# jetson.net
KiCad netlist of a schematic drawn in EAGLE
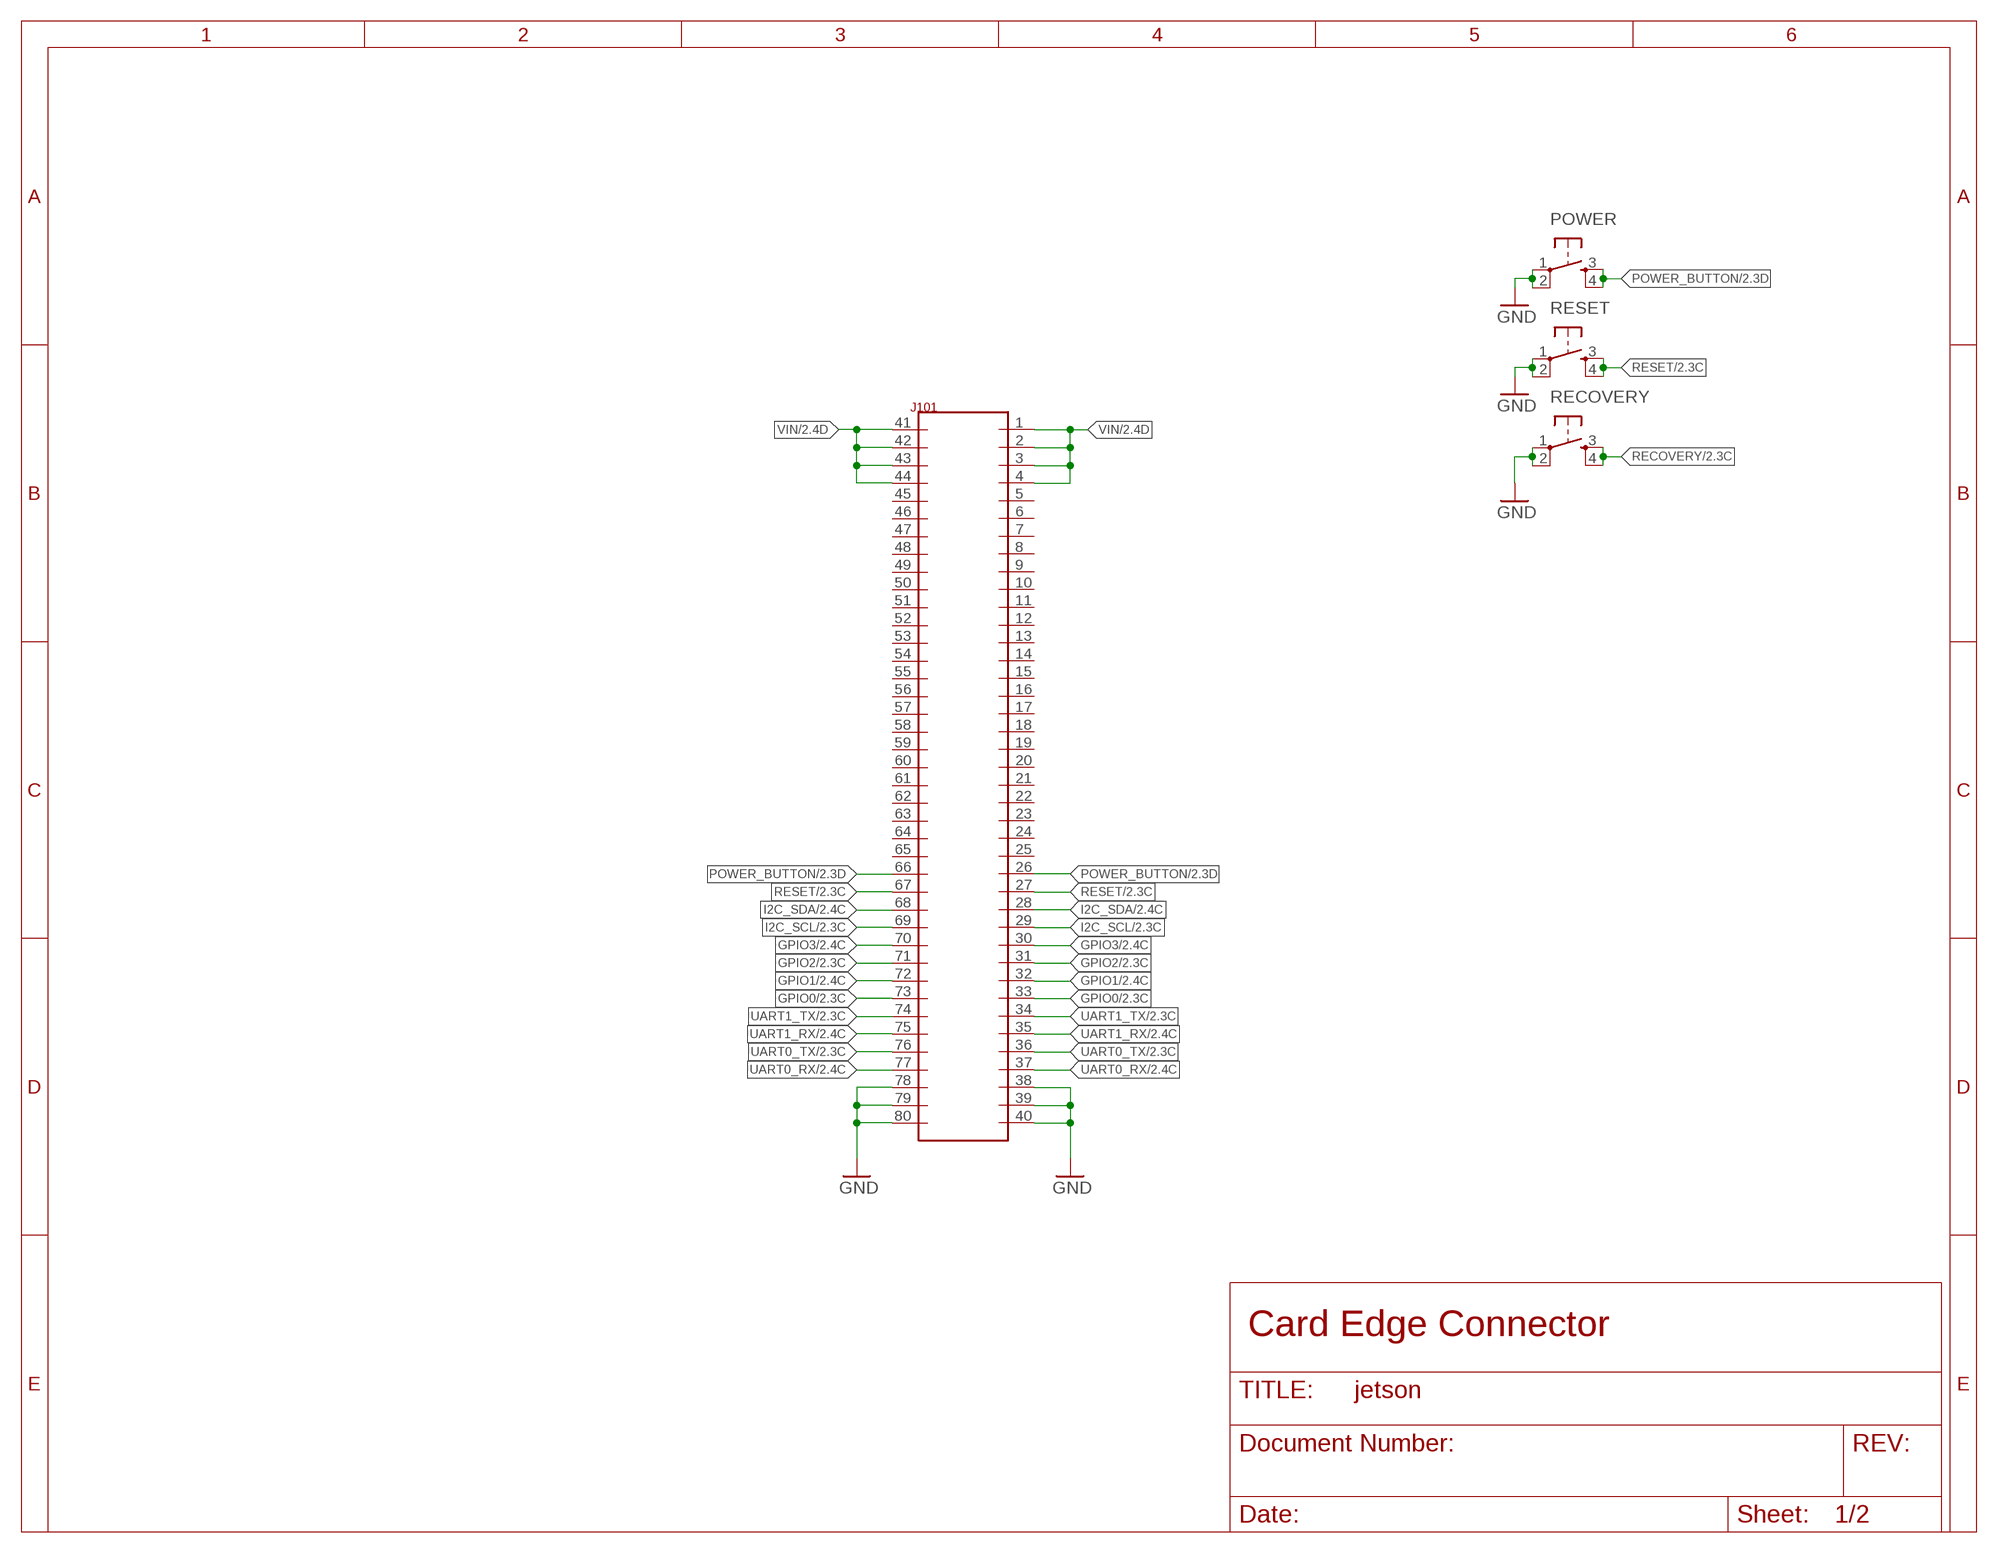
[diagram p0: schematic, sheet 1]
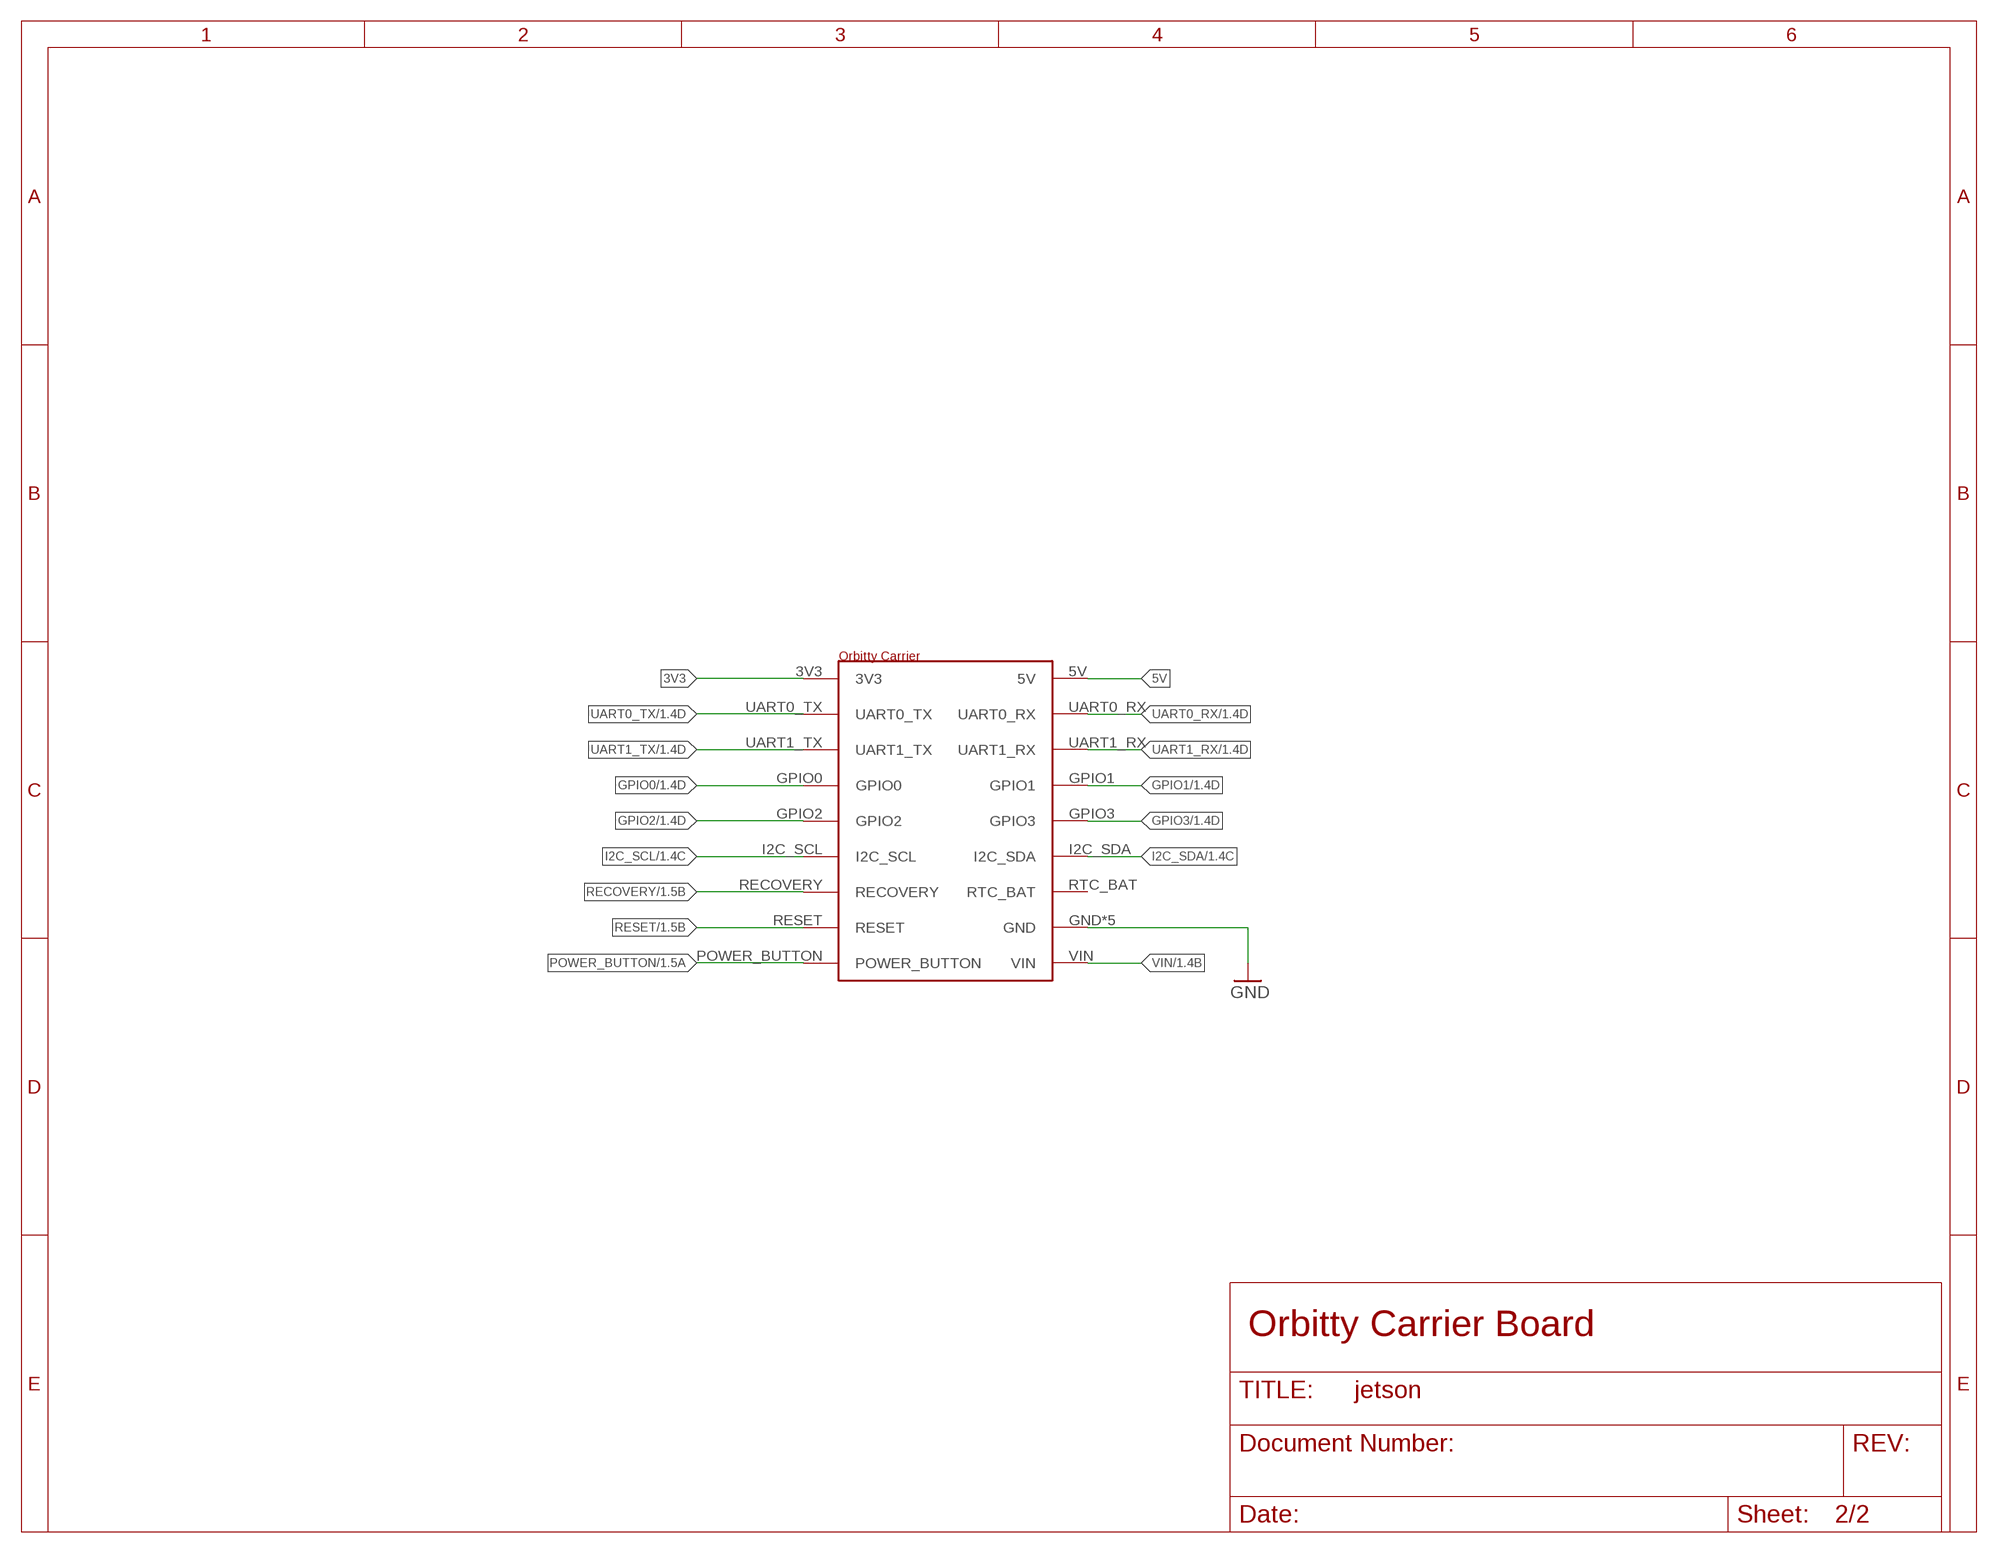
[diagram p1: schematic, sheet 2]

(export (version "E")
  (design (tool "Eeschema 10.0.6"))
  (components
    (comp (ref "U$1")
      (value "ORBITTY_CARRIER")
      (footprint "eagle-import:ORBITTY_CARRIER")
      (libsource (lib "eagle-import") (part "ORBITTY_CARRIER"))
    )
    (comp (ref "J101")
      (value "80-PIN-CARD-EDGE")
      (footprint "eagle-import:80-PIN-CARD-EDGE")
      (libsource (lib "eagle-import") (part "80-PIN-CARD-EDGE"))
    )
    (comp (ref "POWER")
      (value "TAC_SWITCHPTH")
      (footprint "eagle-import:TACTILE-PTH")
      (libsource (lib "eagle-import") (part "TAC_SWITCHPTH"))
    )
    (comp (ref "RECOVERY")
      (value "TAC_SWITCHPTH")
      (footprint "eagle-import:TACTILE-PTH")
      (libsource (lib "eagle-import") (part "TAC_SWITCHPTH"))
    )
    (comp (ref "RESET")
      (value "TAC_SWITCHPTH")
      (footprint "eagle-import:TACTILE-PTH")
      (libsource (lib "eagle-import") (part "TAC_SWITCHPTH"))
    )
  )
  (nets
    (net (code "1") (name "3V3") (class "Default")
      (node (ref "U$1") (pin "3V3") (pinfunction "3V3_3V3") (pintype "bidirectional"))
    )
    (net (code "2") (name "5V") (class "Default")
      (node (ref "U$1") (pin "5V") (pinfunction "5V_5V") (pintype "bidirectional"))
    )
    (net (code "3") (name "GND") (class "Default")
      (node (ref "J101") (pin "38") (pinfunction "P$38_38") (pintype "bidirectional"))
      (node (ref "J101") (pin "39") (pinfunction "P$39_39") (pintype "bidirectional"))
      (node (ref "J101") (pin "40") (pinfunction "P$40_40") (pintype "bidirectional"))
      (node (ref "J101") (pin "78") (pinfunction "P$78_78") (pintype "bidirectional"))
      (node (ref "J101") (pin "79") (pinfunction "P$79_79") (pintype "bidirectional"))
      (node (ref "J101") (pin "80") (pinfunction "P$80_80") (pintype "bidirectional"))
      (node (ref "POWER") (pin "1") (pinfunction "1_1") (pintype "passive"))
      (node (ref "POWER") (pin "2") (pinfunction "2_2") (pintype "passive"))
      (node (ref "RECOVERY") (pin "1") (pinfunction "1_1") (pintype "passive"))
      (node (ref "RECOVERY") (pin "2") (pinfunction "2_2") (pintype "passive"))
      (node (ref "RESET") (pin "1") (pinfunction "1_1") (pintype "passive"))
      (node (ref "RESET") (pin "2") (pinfunction "2_2") (pintype "passive"))
      (node (ref "U$1") (pin "GND") (pinfunction "GND_GND") (pintype "bidirectional"))
      (node (ref "U$1") (pin "GND1") (pinfunction "GND_GND1") (pintype "bidirectional"))
      (node (ref "U$1") (pin "GND2") (pinfunction "GND_GND2") (pintype "bidirectional"))
      (node (ref "U$1") (pin "GND3") (pinfunction "GND_GND3") (pintype "bidirectional"))
      (node (ref "U$1") (pin "GND4") (pinfunction "GND_GND4") (pintype "bidirectional"))
    )
    (net (code "4") (name "GPIO0") (class "Default")
      (node (ref "J101") (pin "33") (pinfunction "P$33_33") (pintype "bidirectional"))
      (node (ref "J101") (pin "73") (pinfunction "P$73_73") (pintype "bidirectional"))
      (node (ref "U$1") (pin "GPIO0") (pinfunction "GPIO0_GPIO0") (pintype "bidirectional"))
    )
    (net (code "5") (name "GPIO1") (class "Default")
      (node (ref "J101") (pin "32") (pinfunction "P$32_32") (pintype "bidirectional"))
      (node (ref "J101") (pin "72") (pinfunction "P$72_72") (pintype "bidirectional"))
      (node (ref "U$1") (pin "GPIO1") (pinfunction "GPIO1_GPIO1") (pintype "bidirectional"))
    )
    (net (code "6") (name "GPIO2") (class "Default")
      (node (ref "J101") (pin "31") (pinfunction "P$31_31") (pintype "bidirectional"))
      (node (ref "J101") (pin "71") (pinfunction "P$71_71") (pintype "bidirectional"))
      (node (ref "U$1") (pin "GPIO2") (pinfunction "GPIO2_GPIO2") (pintype "bidirectional"))
    )
    (net (code "7") (name "GPIO3") (class "Default")
      (node (ref "J101") (pin "30") (pinfunction "P$30_30") (pintype "bidirectional"))
      (node (ref "J101") (pin "70") (pinfunction "P$70_70") (pintype "bidirectional"))
      (node (ref "U$1") (pin "GPIO3") (pinfunction "GPIO3_GPIO3") (pintype "bidirectional"))
    )
    (net (code "8") (name "I2C_SCL") (class "Default")
      (node (ref "J101") (pin "29") (pinfunction "P$29_29") (pintype "bidirectional"))
      (node (ref "J101") (pin "69") (pinfunction "P$69_69") (pintype "bidirectional"))
      (node (ref "U$1") (pin "I2C_SCL") (pinfunction "I2C_SCL_I2C_SCL") (pintype "bidirectional"))
    )
    (net (code "9") (name "I2C_SDA") (class "Default")
      (node (ref "J101") (pin "28") (pinfunction "P$28_28") (pintype "bidirectional"))
      (node (ref "J101") (pin "68") (pinfunction "P$68_68") (pintype "bidirectional"))
      (node (ref "U$1") (pin "I2C_SDA") (pinfunction "I2C_SDA_I2C_SDA") (pintype "bidirectional"))
    )
    (net (code "10") (name "POWER_BUTTON") (class "Default")
      (node (ref "J101") (pin "26") (pinfunction "P$26_26") (pintype "bidirectional"))
      (node (ref "J101") (pin "66") (pinfunction "P$66_66") (pintype "bidirectional"))
      (node (ref "POWER") (pin "3") (pinfunction "3_3") (pintype "passive"))
      (node (ref "POWER") (pin "4") (pinfunction "4_4") (pintype "passive"))
      (node (ref "U$1") (pin "POWER_BUTTON") (pinfunction "POWER_BUTTON_POWER_BUTTON") (pintype "bidirectional"))
    )
    (net (code "11") (name "RECOVERY") (class "Default")
      (node (ref "RECOVERY") (pin "3") (pinfunction "3_3") (pintype "passive"))
      (node (ref "RECOVERY") (pin "4") (pinfunction "4_4") (pintype "passive"))
      (node (ref "U$1") (pin "RECOVERY") (pinfunction "RECOVERY_RECOVERY") (pintype "bidirectional"))
    )
    (net (code "12") (name "RESET") (class "Default")
      (node (ref "J101") (pin "27") (pinfunction "P$27_27") (pintype "bidirectional"))
      (node (ref "J101") (pin "67") (pinfunction "P$67_67") (pintype "bidirectional"))
      (node (ref "RESET") (pin "3") (pinfunction "3_3") (pintype "passive"))
      (node (ref "RESET") (pin "4") (pinfunction "4_4") (pintype "passive"))
      (node (ref "U$1") (pin "RESET") (pinfunction "RESET_RESET") (pintype "bidirectional"))
    )
    (net (code "13") (name "UART0_RX") (class "Default")
      (node (ref "J101") (pin "37") (pinfunction "P$37_37") (pintype "bidirectional"))
      (node (ref "J101") (pin "77") (pinfunction "P$77_77") (pintype "bidirectional"))
      (node (ref "U$1") (pin "UART0_RX") (pinfunction "UART0_RX_UART0_RX") (pintype "bidirectional"))
    )
    (net (code "14") (name "UART0_TX") (class "Default")
      (node (ref "J101") (pin "36") (pinfunction "P$36_36") (pintype "bidirectional"))
      (node (ref "J101") (pin "76") (pinfunction "P$76_76") (pintype "bidirectional"))
      (node (ref "U$1") (pin "UART0_TX") (pinfunction "UART0_TX_UART0_TX") (pintype "bidirectional"))
    )
    (net (code "15") (name "UART1_RX") (class "Default")
      (node (ref "J101") (pin "35") (pinfunction "P$35_35") (pintype "bidirectional"))
      (node (ref "J101") (pin "75") (pinfunction "P$75_75") (pintype "bidirectional"))
      (node (ref "U$1") (pin "UART1_RX") (pinfunction "UART1_RX_UART1_RX") (pintype "bidirectional"))
    )
    (net (code "16") (name "UART1_TX") (class "Default")
      (node (ref "J101") (pin "34") (pinfunction "P$34_34") (pintype "bidirectional"))
      (node (ref "J101") (pin "74") (pinfunction "P$74_74") (pintype "bidirectional"))
      (node (ref "U$1") (pin "UART1_TX") (pinfunction "UART1_TX_UART1_TX") (pintype "bidirectional"))
    )
    (net (code "17") (name "VIN") (class "Default")
      (node (ref "J101") (pin "1") (pinfunction "P$1_1") (pintype "bidirectional"))
      (node (ref "J101") (pin "2") (pinfunction "P$2_2") (pintype "bidirectional"))
      (node (ref "J101") (pin "3") (pinfunction "P$3_3") (pintype "bidirectional"))
      (node (ref "J101") (pin "4") (pinfunction "P$4_4") (pintype "bidirectional"))
      (node (ref "J101") (pin "41") (pinfunction "P$41_41") (pintype "bidirectional"))
      (node (ref "J101") (pin "42") (pinfunction "P$42_42") (pintype "bidirectional"))
      (node (ref "J101") (pin "43") (pinfunction "P$43_43") (pintype "bidirectional"))
      (node (ref "J101") (pin "44") (pinfunction "P$44_44") (pintype "bidirectional"))
      (node (ref "U$1") (pin "VIN") (pinfunction "VIN_VIN") (pintype "bidirectional"))
    )
    (net (code "18") (name "unconnected-(J101-P$5-Pad5)") (class "Default")
      (node (ref "J101") (pin "5") (pinfunction "P$5_5") (pintype "bidirectional"))
    )
    (net (code "19") (name "unconnected-(J101-P$6-Pad6)") (class "Default")
      (node (ref "J101") (pin "6") (pinfunction "P$6_6") (pintype "bidirectional"))
    )
    (net (code "20") (name "unconnected-(J101-P$7-Pad7)") (class "Default")
      (node (ref "J101") (pin "7") (pinfunction "P$7_7") (pintype "bidirectional"))
    )
    (net (code "21") (name "unconnected-(J101-P$8-Pad8)") (class "Default")
      (node (ref "J101") (pin "8") (pinfunction "P$8_8") (pintype "bidirectional"))
    )
    (net (code "22") (name "unconnected-(J101-P$9-Pad9)") (class "Default")
      (node (ref "J101") (pin "9") (pinfunction "P$9_9") (pintype "bidirectional"))
    )
    (net (code "23") (name "unconnected-(J101-P$10-Pad10)") (class "Default")
      (node (ref "J101") (pin "10") (pinfunction "P$10_10") (pintype "bidirectional"))
    )
    (net (code "24") (name "unconnected-(J101-P$11-Pad11)") (class "Default")
      (node (ref "J101") (pin "11") (pinfunction "P$11_11") (pintype "bidirectional"))
    )
    (net (code "25") (name "unconnected-(J101-P$12-Pad12)") (class "Default")
      (node (ref "J101") (pin "12") (pinfunction "P$12_12") (pintype "bidirectional"))
    )
    (net (code "26") (name "unconnected-(J101-P$13-Pad13)") (class "Default")
      (node (ref "J101") (pin "13") (pinfunction "P$13_13") (pintype "bidirectional"))
    )
    (net (code "27") (name "unconnected-(J101-P$14-Pad14)") (class "Default")
      (node (ref "J101") (pin "14") (pinfunction "P$14_14") (pintype "bidirectional"))
    )
    (net (code "28") (name "unconnected-(J101-P$15-Pad15)") (class "Default")
      (node (ref "J101") (pin "15") (pinfunction "P$15_15") (pintype "bidirectional"))
    )
    (net (code "29") (name "unconnected-(J101-P$16-Pad16)") (class "Default")
      (node (ref "J101") (pin "16") (pinfunction "P$16_16") (pintype "bidirectional"))
    )
    (net (code "30") (name "unconnected-(J101-P$17-Pad17)") (class "Default")
      (node (ref "J101") (pin "17") (pinfunction "P$17_17") (pintype "bidirectional"))
    )
    (net (code "31") (name "unconnected-(J101-P$18-Pad18)") (class "Default")
      (node (ref "J101") (pin "18") (pinfunction "P$18_18") (pintype "bidirectional"))
    )
    (net (code "32") (name "unconnected-(J101-P$19-Pad19)") (class "Default")
      (node (ref "J101") (pin "19") (pinfunction "P$19_19") (pintype "bidirectional"))
    )
    (net (code "33") (name "unconnected-(J101-P$20-Pad20)") (class "Default")
      (node (ref "J101") (pin "20") (pinfunction "P$20_20") (pintype "bidirectional"))
    )
    (net (code "34") (name "unconnected-(J101-P$21-Pad21)") (class "Default")
      (node (ref "J101") (pin "21") (pinfunction "P$21_21") (pintype "bidirectional"))
    )
    (net (code "35") (name "unconnected-(J101-P$22-Pad22)") (class "Default")
      (node (ref "J101") (pin "22") (pinfunction "P$22_22") (pintype "bidirectional"))
    )
    (net (code "36") (name "unconnected-(J101-P$23-Pad23)") (class "Default")
      (node (ref "J101") (pin "23") (pinfunction "P$23_23") (pintype "bidirectional"))
    )
    (net (code "37") (name "unconnected-(J101-P$24-Pad24)") (class "Default")
      (node (ref "J101") (pin "24") (pinfunction "P$24_24") (pintype "bidirectional"))
    )
    (net (code "38") (name "unconnected-(J101-P$25-Pad25)") (class "Default")
      (node (ref "J101") (pin "25") (pinfunction "P$25_25") (pintype "bidirectional"))
    )
    (net (code "39") (name "unconnected-(J101-P$45-Pad45)") (class "Default")
      (node (ref "J101") (pin "45") (pinfunction "P$45_45") (pintype "bidirectional"))
    )
    (net (code "40") (name "unconnected-(J101-P$46-Pad46)") (class "Default")
      (node (ref "J101") (pin "46") (pinfunction "P$46_46") (pintype "bidirectional"))
    )
    (net (code "41") (name "unconnected-(J101-P$47-Pad47)") (class "Default")
      (node (ref "J101") (pin "47") (pinfunction "P$47_47") (pintype "bidirectional"))
    )
    (net (code "42") (name "unconnected-(J101-P$48-Pad48)") (class "Default")
      (node (ref "J101") (pin "48") (pinfunction "P$48_48") (pintype "bidirectional"))
    )
    (net (code "43") (name "unconnected-(J101-P$49-Pad49)") (class "Default")
      (node (ref "J101") (pin "49") (pinfunction "P$49_49") (pintype "bidirectional"))
    )
    (net (code "44") (name "unconnected-(J101-P$50-Pad50)") (class "Default")
      (node (ref "J101") (pin "50") (pinfunction "P$50_50") (pintype "bidirectional"))
    )
    (net (code "45") (name "unconnected-(J101-P$51-Pad51)") (class "Default")
      (node (ref "J101") (pin "51") (pinfunction "P$51_51") (pintype "bidirectional"))
    )
    (net (code "46") (name "unconnected-(J101-P$52-Pad52)") (class "Default")
      (node (ref "J101") (pin "52") (pinfunction "P$52_52") (pintype "bidirectional"))
    )
    (net (code "47") (name "unconnected-(J101-P$53-Pad53)") (class "Default")
      (node (ref "J101") (pin "53") (pinfunction "P$53_53") (pintype "bidirectional"))
    )
    (net (code "48") (name "unconnected-(J101-P$54-Pad54)") (class "Default")
      (node (ref "J101") (pin "54") (pinfunction "P$54_54") (pintype "bidirectional"))
    )
    (net (code "49") (name "unconnected-(J101-P$55-Pad55)") (class "Default")
      (node (ref "J101") (pin "55") (pinfunction "P$55_55") (pintype "bidirectional"))
    )
    (net (code "50") (name "unconnected-(J101-P$56-Pad56)") (class "Default")
      (node (ref "J101") (pin "56") (pinfunction "P$56_56") (pintype "bidirectional"))
    )
    (net (code "51") (name "unconnected-(J101-P$57-Pad57)") (class "Default")
      (node (ref "J101") (pin "57") (pinfunction "P$57_57") (pintype "bidirectional"))
    )
    (net (code "52") (name "unconnected-(J101-P$58-Pad58)") (class "Default")
      (node (ref "J101") (pin "58") (pinfunction "P$58_58") (pintype "bidirectional"))
    )
    (net (code "53") (name "unconnected-(J101-P$59-Pad59)") (class "Default")
      (node (ref "J101") (pin "59") (pinfunction "P$59_59") (pintype "bidirectional"))
    )
    (net (code "54") (name "unconnected-(J101-P$60-Pad60)") (class "Default")
      (node (ref "J101") (pin "60") (pinfunction "P$60_60") (pintype "bidirectional"))
    )
    (net (code "55") (name "unconnected-(J101-P$61-Pad61)") (class "Default")
      (node (ref "J101") (pin "61") (pinfunction "P$61_61") (pintype "bidirectional"))
    )
    (net (code "56") (name "unconnected-(J101-P$62-Pad62)") (class "Default")
      (node (ref "J101") (pin "62") (pinfunction "P$62_62") (pintype "bidirectional"))
    )
    (net (code "57") (name "unconnected-(J101-P$63-Pad63)") (class "Default")
      (node (ref "J101") (pin "63") (pinfunction "P$63_63") (pintype "bidirectional"))
    )
    (net (code "58") (name "unconnected-(J101-P$64-Pad64)") (class "Default")
      (node (ref "J101") (pin "64") (pinfunction "P$64_64") (pintype "bidirectional"))
    )
    (net (code "59") (name "unconnected-(J101-P$65-Pad65)") (class "Default")
      (node (ref "J101") (pin "65") (pinfunction "P$65_65") (pintype "bidirectional"))
    )
    (net (code "60") (name "unconnected-(U$1-PadRTC_BAT)") (class "Default")
      (node (ref "U$1") (pin "RTC_BAT") (pinfunction "RTC_BAT_RTC_BAT") (pintype "bidirectional"))
    )
  )
)
